# digitaalitekniikka_555_blinker.net
KiCad netlist of a schematic drawn in EAGLE
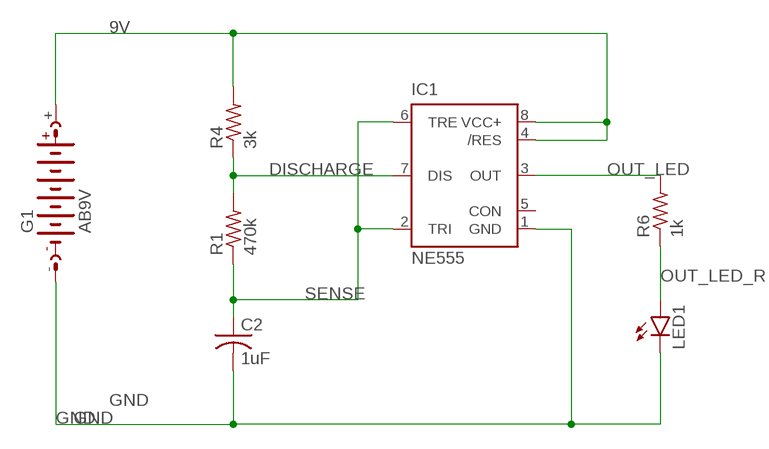
[diagram p0: schematic, sheet 1]

(export (version "E")
  (design (tool "Eeschema 10.0.6"))
  (components
    (comp (ref "C2")
      (value "1uF")
      (footprint "eagle-import:C0805")
      (libsource (lib "eagle-import") (part "C-USC0805"))
    )
    (comp (ref "G1")
      (value "AB9V")
      (footprint "eagle-import:AB9V")
      (libsource (lib "eagle-import") (part "AB9V"))
    )
    (comp (ref "IC1")
      (value "NE555")
      (footprint "eagle-import:DIL-08")
      (fields (field (name "MF") "Arrow Electronics") (field (name "MPN") "NE555N"))
      (libsource (lib "eagle-import") (part "NE555"))
    )
    (comp (ref "LED1")
      (value "LEDCHIPLED_0805")
      (footprint "eagle-import:CHIPLED_0805")
      (libsource (lib "eagle-import") (part "LEDCHIPLED_0805"))
    )
    (comp (ref "R1")
      (value "470k")
      (footprint "eagle-import:R0805")
      (libsource (lib "eagle-import") (part "R-US_R0805"))
    )
    (comp (ref "R4")
      (value "3k")
      (footprint "eagle-import:R0805")
      (libsource (lib "eagle-import") (part "R-US_R0805"))
    )
    (comp (ref "R6")
      (value "1k")
      (footprint "eagle-import:R0805")
      (libsource (lib "eagle-import") (part "R-US_R0805"))
    )
  )
  (nets
    (net (code "1") (name "/9V") (class "Default")
      (node (ref "G1") (pin "+") (pinfunction "+_+") (pintype "passive"))
      (node (ref "IC1") (pin "4") (pinfunction "/RES_4") (pintype "input"))
      (node (ref "IC1") (pin "8") (pinfunction "VCC+_8") (pintype "power_in"))
      (node (ref "R4") (pin "2") (pinfunction "2_2") (pintype "passive"))
    )
    (net (code "2") (name "/DISCHARGE") (class "Default")
      (node (ref "IC1") (pin "7") (pinfunction "DIS_7") (pintype "input"))
      (node (ref "R1") (pin "2") (pinfunction "2_2") (pintype "passive"))
      (node (ref "R4") (pin "1") (pinfunction "1_1") (pintype "passive"))
    )
    (net (code "3") (name "/GND") (class "Default")
      (node (ref "C2") (pin "2") (pinfunction "2_2") (pintype "passive"))
      (node (ref "G1") (pin "-") (pinfunction "-_-") (pintype "passive"))
      (node (ref "IC1") (pin "1") (pinfunction "GND_1") (pintype "power_in"))
      (node (ref "LED1") (pin "C") (pinfunction "C_C") (pintype "passive"))
    )
    (net (code "4") (name "/OUT_LED") (class "Default")
      (node (ref "IC1") (pin "3") (pinfunction "OUT_3") (pintype "output"))
      (node (ref "R6") (pin "2") (pinfunction "2_2") (pintype "passive"))
    )
    (net (code "5") (name "/OUT_LED_R") (class "Default")
      (node (ref "LED1") (pin "A") (pinfunction "A_A") (pintype "passive"))
      (node (ref "R6") (pin "1") (pinfunction "1_1") (pintype "passive"))
    )
    (net (code "6") (name "/SENSE") (class "Default")
      (node (ref "C2") (pin "1") (pinfunction "1_1") (pintype "passive"))
      (node (ref "IC1") (pin "2") (pinfunction "TRI_2") (pintype "input"))
      (node (ref "IC1") (pin "6") (pinfunction "TRE_6") (pintype "input"))
      (node (ref "R1") (pin "1") (pinfunction "1_1") (pintype "passive"))
    )
    (net (code "7") (name "unconnected-(IC1-CON-Pad5)") (class "Default")
      (node (ref "IC1") (pin "5") (pinfunction "CON_5") (pintype "input"))
    )
  )
)
